# PicoHAL.net
KiCad netlist of a schematic drawn in Altium Designer
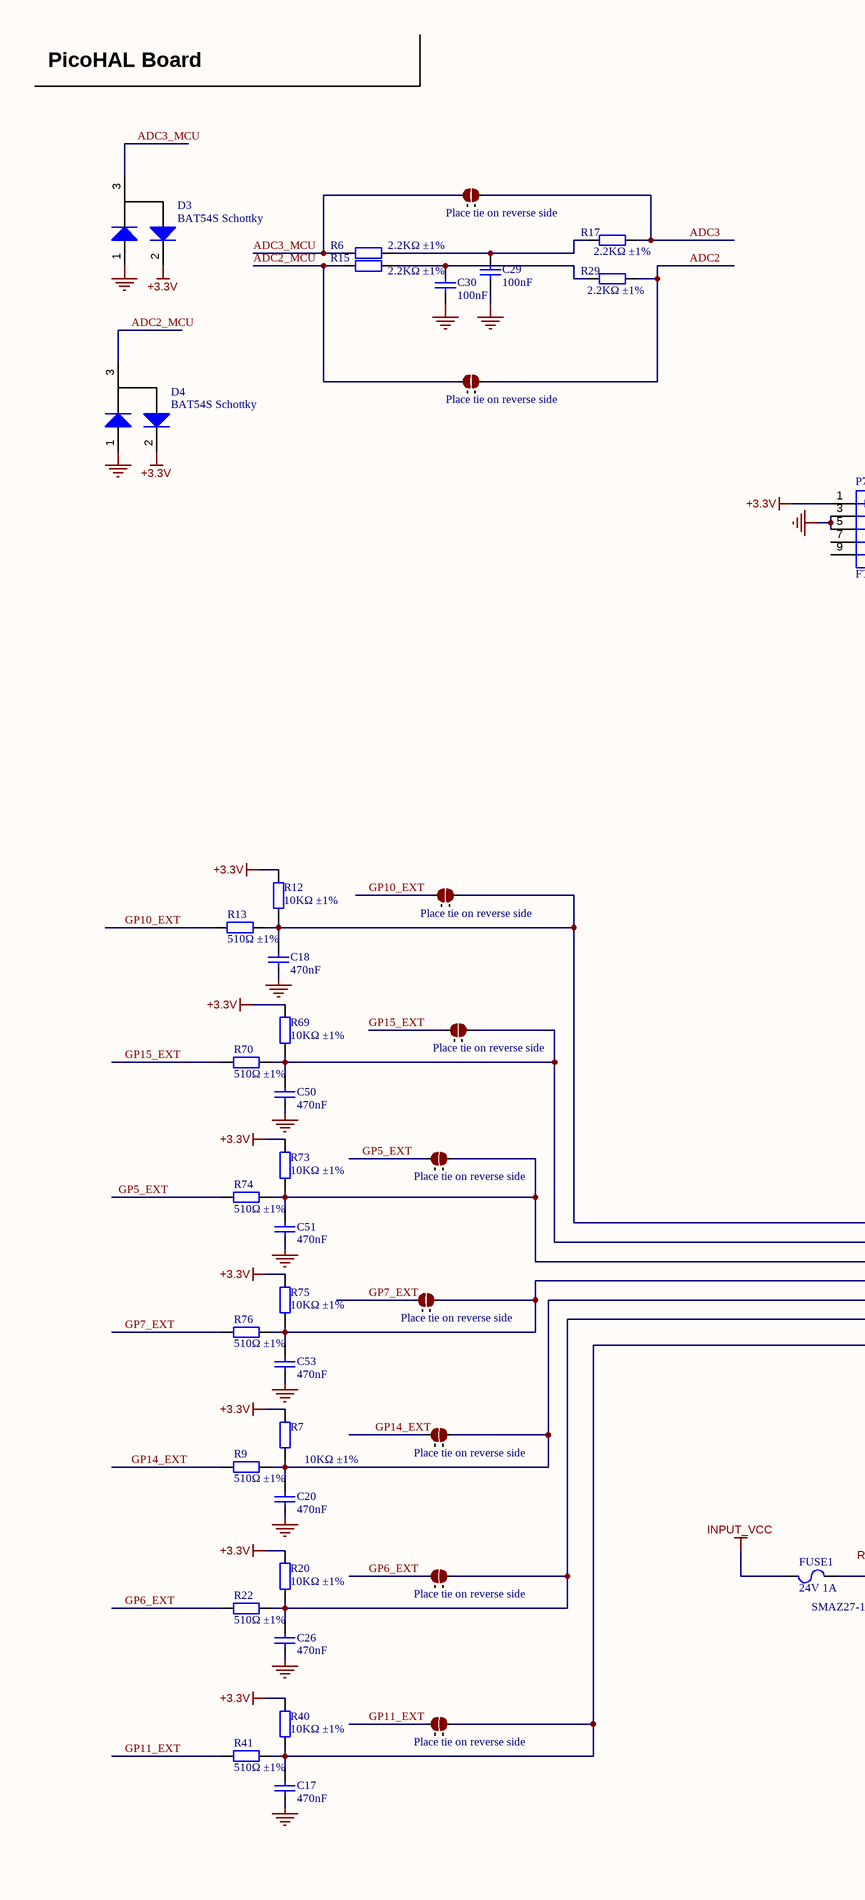
[diagram p0: PicoHAL.SchDoc, left]
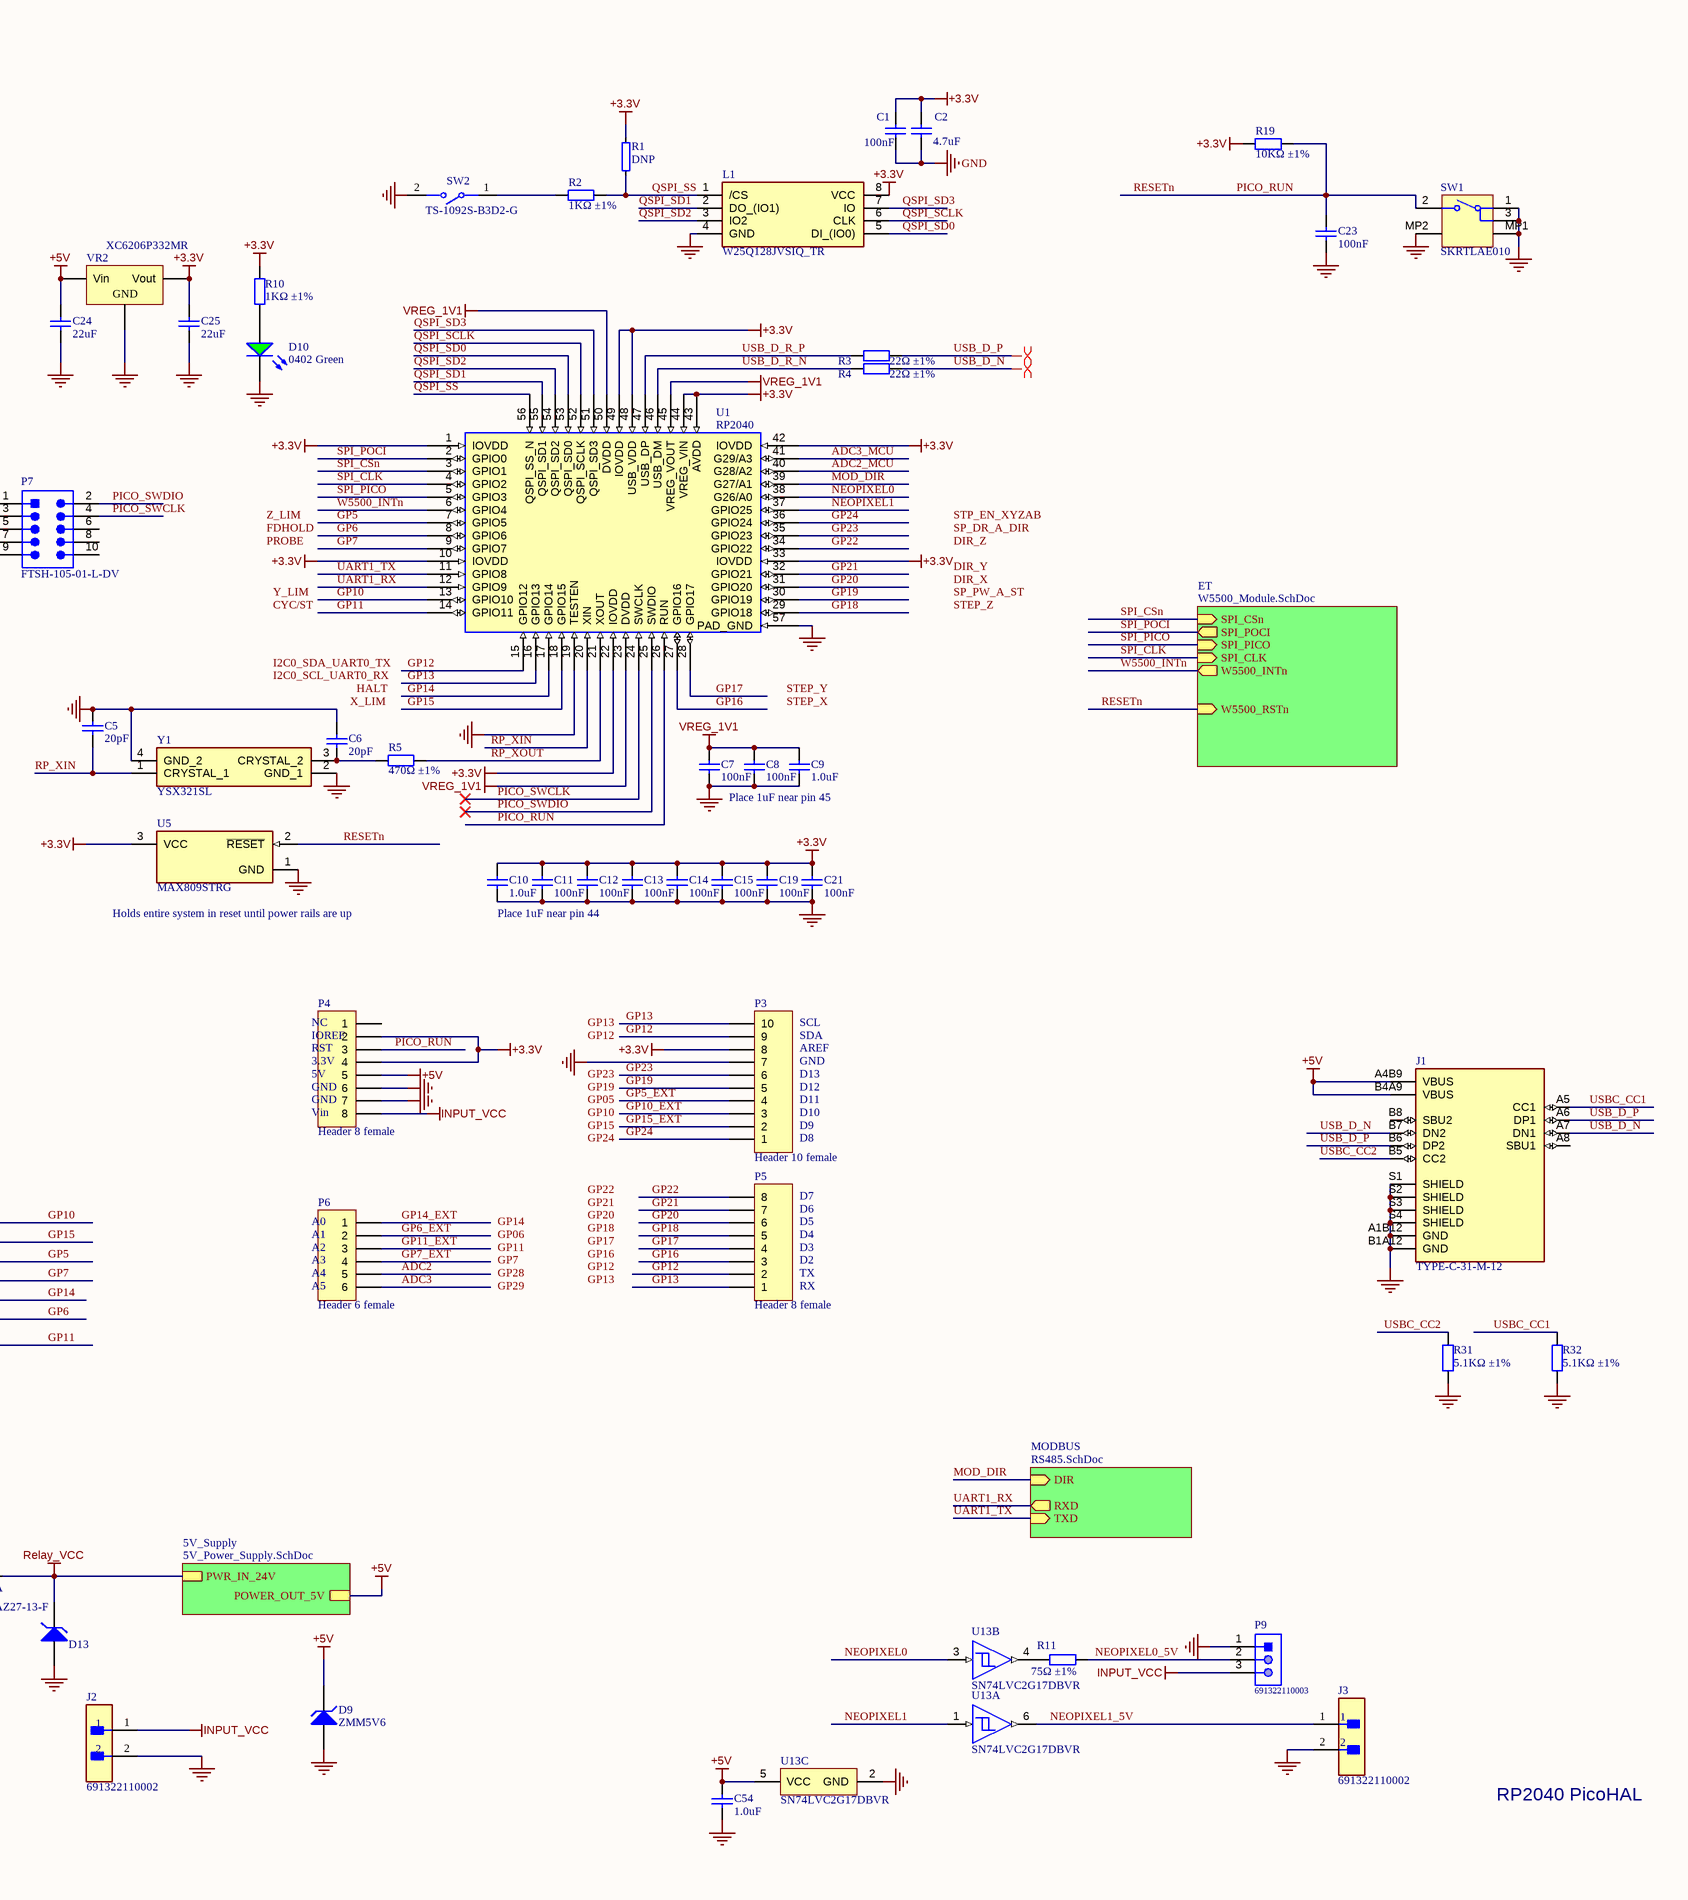
[diagram p1: PicoHAL.SchDoc, right]

(export (version "E")
  (design (tool "Eeschema 10.0.6"))
  (components
    (comp (ref "C1")
      (value "100nF")
      (footprint "0402_C")
      (description "Chip capacitors")
      (fields
        (field (name "MANUFACTURER") "Samsung Electro-Mechanics")
        (field (name "PARTNUMBER") "CL05B104KO5NNNC")
      )
      (libsource (lib "Cap") (part "0402 100nF (104) 10% 16V"))
    )
    (comp (ref "C2")
      (value "4.7uF")
      (footprint "0402_C")
      (description "Chip capacitor")
      (fields
        (field (name "MANUFACTURER") "Samsung Electro-Mechanics")
        (field (name "PARTNUMBER") "CL05A475MP5NRNC")
      )
      (libsource (lib "Cap") (part "0402 4.7uF (475) 20% 10V"))
    )
    (comp (ref "C5")
      (value "20pF")
      (footprint "0402_C")
      (description "Chip capacitors")
      (fields
        (field (name "MANUFACTURER") "Guangdong Fenghua Advanced Tech")
        (field (name "PARTNUMBER") "0402CG200J500NT")
      )
      (libsource (lib "Cap") (part "0402 20pF (200) 5% 50V"))
    )
    (comp (ref "C6")
      (value "20pF")
      (footprint "0402_C")
      (description "Chip capacitors")
      (fields
        (field (name "MANUFACTURER") "Guangdong Fenghua Advanced Tech")
        (field (name "PARTNUMBER") "0402CG200J500NT")
      )
      (libsource (lib "Cap") (part "0402 20pF (200) 5% 50V"))
    )
    (comp (ref "C7")
      (value "100nF")
      (footprint "0402_C")
      (description "Chip capacitors")
      (fields
        (field (name "MANUFACTURER") "Samsung Electro-Mechanics")
        (field (name "PARTNUMBER") "CL05B104KO5NNNC")
      )
      (libsource (lib "Cap") (part "0402 100nF (104) 10% 16V"))
    )
    (comp (ref "C8")
      (value "100nF")
      (footprint "0402_C")
      (description "Chip capacitors")
      (fields
        (field (name "MANUFACTURER") "Samsung Electro-Mechanics")
        (field (name "PARTNUMBER") "CL05B104KO5NNNC")
      )
      (libsource (lib "Cap") (part "0402 100nF (104) 10% 16V"))
    )
    (comp (ref "C9")
      (value "1.0uF")
      (footprint "0402_C")
      (description "Chip capacitor")
      (fields
        (field (name "MANUFACTURER") "Samsung Electro-Mechanics")
        (field (name "PARTNUMBER") "CL05A105KA5NQNC")
      )
      (libsource (lib "Cap") (part "0402 1.0uF (105) 10% 25V"))
    )
    (comp (ref "C10")
      (value "1.0uF")
      (footprint "0402_C")
      (description "Chip capacitor")
      (fields
        (field (name "MANUFACTURER") "Samsung Electro-Mechanics")
        (field (name "PARTNUMBER") "CL05A105KA5NQNC")
      )
      (libsource (lib "Cap") (part "0402 1.0uF (105) 10% 25V"))
    )
    (comp (ref "C11")
      (value "100nF")
      (footprint "0402_C")
      (description "Chip capacitors")
      (fields
        (field (name "MANUFACTURER") "Samsung Electro-Mechanics")
        (field (name "PARTNUMBER") "CL05B104KO5NNNC")
      )
      (libsource (lib "Cap") (part "0402 100nF (104) 10% 16V"))
    )
    (comp (ref "C12")
      (value "100nF")
      (footprint "0402_C")
      (description "Chip capacitors")
      (fields
        (field (name "MANUFACTURER") "Samsung Electro-Mechanics")
        (field (name "PARTNUMBER") "CL05B104KO5NNNC")
      )
      (libsource (lib "Cap") (part "0402 100nF (104) 10% 16V"))
    )
    (comp (ref "C13")
      (value "100nF")
      (footprint "0402_C")
      (description "Chip capacitors")
      (fields
        (field (name "MANUFACTURER") "Samsung Electro-Mechanics")
        (field (name "PARTNUMBER") "CL05B104KO5NNNC")
      )
      (libsource (lib "Cap") (part "0402 100nF (104) 10% 16V"))
    )
    (comp (ref "C14")
      (value "100nF")
      (footprint "0402_C")
      (description "Chip capacitors")
      (fields
        (field (name "MANUFACTURER") "Samsung Electro-Mechanics")
        (field (name "PARTNUMBER") "CL05B104KO5NNNC")
      )
      (libsource (lib "Cap") (part "0402 100nF (104) 10% 16V"))
    )
    (comp (ref "C15")
      (value "100nF")
      (footprint "0402_C")
      (description "Chip capacitors")
      (fields
        (field (name "MANUFACTURER") "Samsung Electro-Mechanics")
        (field (name "PARTNUMBER") "CL05B104KO5NNNC")
      )
      (libsource (lib "Cap") (part "0402 100nF (104) 10% 16V"))
    )
    (comp (ref "C17")
      (value "470nF")
      (footprint "0402_C")
      (description "Chip capacitors")
      (fields
        (field (name "MANUFACTURER") "Samsung Electro-Mechanics")
        (field (name "PARTNUMBER") "CL05A474KP5NNNC")
      )
      (libsource (lib "Cap") (part "0402 470nF (474) 10% 10V"))
    )
    (comp (ref "C18")
      (value "470nF")
      (footprint "0402_C")
      (description "Chip capacitors")
      (fields
        (field (name "MANUFACTURER") "Samsung Electro-Mechanics")
        (field (name "PARTNUMBER") "CL05A474KP5NNNC")
      )
      (libsource (lib "Cap") (part "0402 470nF (474) 10% 10V"))
    )
    (comp (ref "C19")
      (value "100nF")
      (footprint "0402_C")
      (description "Chip capacitors")
      (fields
        (field (name "MANUFACTURER") "Samsung Electro-Mechanics")
        (field (name "PARTNUMBER") "CL05B104KO5NNNC")
      )
      (libsource (lib "Cap") (part "0402 100nF (104) 10% 16V"))
    )
    (comp (ref "C20")
      (value "470nF")
      (footprint "0402_C")
      (description "Chip capacitors")
      (fields
        (field (name "MANUFACTURER") "Samsung Electro-Mechanics")
        (field (name "PARTNUMBER") "CL05A474KP5NNNC")
      )
      (libsource (lib "Cap") (part "0402 470nF (474) 10% 10V"))
    )
    (comp (ref "C21")
      (value "100nF")
      (footprint "0402_C")
      (description "Chip capacitors")
      (fields
        (field (name "MANUFACTURER") "Samsung Electro-Mechanics")
        (field (name "PARTNUMBER") "CL05B104KO5NNNC")
      )
      (libsource (lib "Cap") (part "0402 100nF (104) 10% 16V"))
    )
    (comp (ref "C23")
      (value "100nF")
      (footprint "0402_C")
      (description "Chip capacitors")
      (fields
        (field (name "MANUFACTURER") "Samsung Electro-Mechanics")
        (field (name "PARTNUMBER") "CL05B104KO5NNNC")
      )
      (libsource (lib "Cap") (part "0402 100nF (104) 10% 16V"))
    )
    (comp (ref "C24")
      (value "22uF")
      (footprint "0805_C")
      (description "Chip capacitors")
      (fields
        (field (name "MANUFACTURER") "Samsung Electro-Mechanics")
        (field (name "PARTNUMBER") "CL21A226MAQNNNE")
      )
      (libsource (lib "Cap") (part "0805 22uF (226) 20% 25V"))
    )
    (comp (ref "C25")
      (value "22uF")
      (footprint "0805_C")
      (description "Chip capacitors")
      (fields
        (field (name "MANUFACTURER") "Samsung Electro-Mechanics")
        (field (name "PARTNUMBER") "CL21A226MAQNNNE")
      )
      (libsource (lib "Cap") (part "0805 22uF (226) 20% 25V"))
    )
    (comp (ref "C26")
      (value "470nF")
      (footprint "0402_C")
      (description "Chip capacitors")
      (fields
        (field (name "MANUFACTURER") "Samsung Electro-Mechanics")
        (field (name "PARTNUMBER") "CL05A474KP5NNNC")
      )
      (libsource (lib "Cap") (part "0402 470nF (474) 10% 10V"))
    )
    (comp (ref "C29")
      (value "100nF")
      (footprint "0402_C")
      (description "Chip capacitors")
      (fields
        (field (name "MANUFACTURER") "Samsung Electro-Mechanics")
        (field (name "PARTNUMBER") "CL05B104KO5NNNC")
      )
      (libsource (lib "Cap") (part "0402 100nF (104) 10% 16V"))
    )
    (comp (ref "C30")
      (value "100nF")
      (footprint "0402_C")
      (description "Chip capacitors")
      (fields
        (field (name "MANUFACTURER") "Samsung Electro-Mechanics")
        (field (name "PARTNUMBER") "CL05B104KO5NNNC")
      )
      (libsource (lib "Cap") (part "0402 100nF (104) 10% 16V"))
    )
    (comp (ref "C50")
      (value "470nF")
      (footprint "0402_C")
      (description "Chip capacitors")
      (fields
        (field (name "MANUFACTURER") "Samsung Electro-Mechanics")
        (field (name "PARTNUMBER") "CL05A474KP5NNNC")
      )
      (libsource (lib "Cap") (part "0402 470nF (474) 10% 10V"))
    )
    (comp (ref "C51")
      (value "470nF")
      (footprint "0402_C")
      (description "Chip capacitors")
      (fields
        (field (name "MANUFACTURER") "Samsung Electro-Mechanics")
        (field (name "PARTNUMBER") "CL05A474KP5NNNC")
      )
      (libsource (lib "Cap") (part "0402 470nF (474) 10% 10V"))
    )
    (comp (ref "C53")
      (value "470nF")
      (footprint "0402_C")
      (description "Chip capacitors")
      (fields
        (field (name "MANUFACTURER") "Samsung Electro-Mechanics")
        (field (name "PARTNUMBER") "CL05A474KP5NNNC")
      )
      (libsource (lib "Cap") (part "0402 470nF (474) 10% 10V"))
    )
    (comp (ref "C54")
      (value "1.0uF")
      (footprint "0402_C")
      (description "Chip capacitor")
      (fields
        (field (name "MANUFACTURER") "Samsung Electro-Mechanics")
        (field (name "PARTNUMBER") "CL05A105KA5NQNC")
      )
      (libsource (lib "Cap") (part "0402 1.0uF (105) 10% 25V"))
    )
    (comp (ref "D3")
      (value "BAT54S Schottky")
      (footprint "SOT-23(SOT-23-3)")
      (description "30V Dual 200mA 800mV@100mA SOT-23 Schottky Barrier Diodes (SBD) ROHS")
      (libsource (lib "Diode") (part "SOT-23 BAT54S"))
    )
    (comp (ref "D4")
      (value "BAT54S Schottky")
      (footprint "SOT-23(SOT-23-3)")
      (description "30V Dual 200mA 800mV@100mA SOT-23 Schottky Barrier Diodes (SBD) ROHS")
      (libsource (lib "Diode") (part "SOT-23 BAT54S"))
    )
    (comp (ref "D9")
      (value "ZMM5V6")
      (footprint "LL-34")
      (description "500mW - 0.1uA @ 1V 5.6V LL-34 Zener Diodes ROHS")
      (libsource (lib "Zener") (part "LL-34 ZMM5V6"))
    )
    (comp (ref "D10")
      (value "0402 Green")
      (footprint "LED 0402_1005 RED")
      (description "LED")
      (libsource (lib "LED") (part "0402 LED Green"))
    )
    (comp (ref "D13")
      (value "SMAZ27-13-F")
      (footprint "DIOM5226X240N")
      (description "27V ±5% 1W 500nA @ 20.5V SMA(DO-214AC) Zener Diodes RoHS")
      (libsource (lib "PrintNC_GRBLHAL_Breakout") (part "BZT52C27"))
    )
    (comp (ref "FUSE1")
      (value "24V 1A")
      (footprint "1206_C")
      (description "24V 1A 0.1s 1206 PTC Resettable Fuses RoHS")
      (fields
        (field (name "MANUFACTURER") "Jinrui Electronic Materials Co.")
        (field (name "PARTNUMBER") "JK-nSMD050-24")
      )
      (libsource (lib "PrintNC_GRBLHAL_Breakout") (part "JK-nSMD050-24"))
    )
    (comp (ref "J1")
      (value "TYPE-C-31-M-12")
      (footprint "HRO_TYPE-C-31-M-12")
      (description "USB Connectors 24 Receptacle 1 8.94*7.3mm RoHS")
      (fields (field (name "MF") "HRO Electronics Co., Ltd."))
      (libsource (lib "Universal_CNC_Breakout") (part "TYPE-C-31-M-12"))
    )
    (comp (ref "J2")
      (value "691322110002")
      (footprint "FP-691322110002-MFG")
      (description "TERM BLOCK HDR 2POS 90DEG 3.5MM")
      (fields (field (name "VOLTAGE") "300V"))
      (libsource (lib "") (part "3bc925449376181038e59eaffc5286c_1"))
    )
    (comp (ref "J3")
      (value "691322110002")
      (footprint "FP-691322110002-MFG")
      (description "TERM BLOCK HDR 2POS 90DEG 3.5MM")
      (libsource (lib "Altium Content Vault") (part "3bc925449376181038e59eaffc5286c"))
    )
    (comp (ref "J7")
      (value "2 way net solder junction - Normally Open")
      (footprint "2waySolder_NO")
      (libsource (lib "PrintNC_GRBLHAL_Breakout") (part "2waySolderNO"))
    )
    (comp (ref "J8")
      (value "2 way net solder junction - Normally Open")
      (footprint "2waySolder_NO")
      (libsource (lib "PrintNC_GRBLHAL_Breakout") (part "2waySolderNO"))
    )
    (comp (ref "J9")
      (value "2 way net solder junction - Normally Open")
      (footprint "2waySolder_NO")
      (libsource (lib "PrintNC_GRBLHAL_Breakout") (part "2waySolderNO"))
    )
    (comp (ref "J10")
      (value "2 way net solder junction - Normally Open")
      (footprint "2waySolder_NO")
      (libsource (lib "PrintNC_GRBLHAL_Breakout") (part "2waySolderNO"))
    )
    (comp (ref "J11")
      (value "2 way net solder junction - Normally Open")
      (footprint "2waySolder_NO")
      (libsource (lib "PrintNC_GRBLHAL_Breakout") (part "2waySolderNO"))
    )
    (comp (ref "J12")
      (value "2 way net solder junction - Normally Open")
      (footprint "2waySolder_NO")
      (libsource (lib "PrintNC_GRBLHAL_Breakout") (part "2waySolderNO"))
    )
    (comp (ref "J13")
      (value "2 way net solder junction - Normally Open")
      (footprint "2waySolder_NO")
      (libsource (lib "PrintNC_GRBLHAL_Breakout") (part "2waySolderNO"))
    )
    (comp (ref "J14")
      (value "2 way net solder junction - Normally Open")
      (footprint "2waySolder_NO")
      (libsource (lib "PrintNC_GRBLHAL_Breakout") (part "2waySolderNO"))
    )
    (comp (ref "J15")
      (value "2 way net solder junction - Normally Open")
      (footprint "2waySolder_NO")
      (libsource (lib "PrintNC_GRBLHAL_Breakout") (part "2waySolderNO"))
    )
    (comp (ref "L1")
      (value "W25Q128JVSIQ_TR")
      (footprint "SamacSys:SOIC127P780X195-8N")
      (description "Inductor")
      (fields
        (field (name "MANUFACTURER_PART_NUMBER") "W25Q128JVSIQ TR")
        (field (name "MOUSER PART NUMBER") "454-W25Q128JVSIQTR")
      )
      (libsource (lib "*") (part "W25Q128JVSIQ_TR"))
    )
    (comp (ref "P3")
      (value "Header 10 female")
      (footprint "HDR1X10")
      (description "Header, 10-Pin")
      (fields (field (name "PUBLISHER") "Altium Limited"))
      (libsource (lib "Miscellaneous Connectors") (part "Header 10"))
    )
    (comp (ref "P4")
      (value "Header 8 female")
      (footprint "HDR1X8")
      (description "Header, 8-Pin")
      (fields (field (name "PUBLISHER") "Altium Limited"))
      (libsource (lib "") (part "Header 8_1"))
    )
    (comp (ref "P5")
      (value "Header 8 female")
      (footprint "HDR1X8")
      (description "Header, 8-Pin")
      (fields (field (name "PUBLISHER") "Altium Limited"))
      (libsource (lib "Miscellaneous Connectors") (part "Header 8"))
    )
    (comp (ref "P6")
      (value "Header 6 female")
      (footprint "HDR1X6")
      (description "Header, 6-Pin")
      (fields (field (name "PUBLISHER") "Altium Limited"))
      (libsource (lib "Miscellaneous Connectors") (part "Header 6"))
    )
    (comp (ref "P7")
      (value "FTSH-105-01-L-DV")
      (footprint "SMTC-FTSH-105-01-L-DV_V")
      (description "Male Header, Pitch 1.27 mm, 2 x 5 Position, Height 5.96 mm, -55 to 125 degC, RoHS, Bulk")
      (fields (field (name "MANUFACTURER") "Samtec"))
      (libsource (lib "Altium Content Vault") (part "CN-2P-M-R10"))
    )
    (comp (ref "P9")
      (value "691322110003")
      (footprint "691322110003")
      (description "Serie 3221 - 3.50mm Horizontal PCB Header WR-TBL, 3 pin")
      (libsource (lib "Altium Content Vault") (part "WE-CN-1P-M-R3"))
    )
    (comp (ref "R1")
      (value "DNP")
      (footprint "0402")
      (description "Resistor, ±5%, 0.05W")
      (fields (field (name "PART NUMBER") "R0201-0R") (field (name "PUBLISHER") "Nordic Semiconductor"))
      (libsource (lib "Passives") (part "RES"))
    )
    (comp (ref "R2")
      (value "1KΩ ±1%")
      (footprint "0402_R")
      (description "Chip resistor")
      (fields (field (name "MANUFACTURER") "Uniroyal Elec") (field (name "PARTNUMBER") "0402WGF1001TCE"))
      (libsource (lib "RES") (part "0402 1K (1001) 1%"))
    )
    (comp (ref "R3")
      (value "22Ω ±1%")
      (footprint "0402_R")
      (description "Chip resistor")
      (fields (field (name "MANUFACTURER") "Uniroyal Elec") (field (name "PARTNUMBER") "0402WGF220JTCE"))
      (libsource (lib "RES") (part "0402 22R (22R0) 1%"))
    )
    (comp (ref "R4")
      (value "22Ω ±1%")
      (footprint "0402_R")
      (description "Chip resistor")
      (fields (field (name "MANUFACTURER") "Uniroyal Elec") (field (name "PARTNUMBER") "0402WGF220JTCE"))
      (libsource (lib "RES") (part "0402 22R (22R0) 1%"))
    )
    (comp (ref "R5")
      (value "470Ω ±1%")
      (footprint "0402_R")
      (description "Chip resistor")
      (fields (field (name "MANUFACTURER") "Uniroyal Elec") (field (name "PARTNUMBER") "0402WGF4700TCE"))
      (libsource (lib "RES") (part "0402 470R (4700) 1%"))
    )
    (comp (ref "R6")
      (value "2.2KΩ ±1%")
      (footprint "0402_R")
      (description "Chip resistor")
      (fields (field (name "MANUFACTURER") "Uniroyal Elec") (field (name "PARTNUMBER") "0402WGF2201TCE"))
      (libsource (lib "RES") (part "0402 2.2K (2201) 1%"))
    )
    (comp (ref "R7")
      (value "10KΩ ±1%")
      (footprint "0402_R")
      (description "Chip resistor")
      (fields (field (name "MANUFACTURER") "Uniroyal Elec") (field (name "PARTNUMBER") "0402WGF1002TCE"))
      (libsource (lib "RES") (part "0402 10K (1002) 1%"))
    )
    (comp (ref "R9")
      (value "510Ω ±1%")
      (footprint "0402_R")
      (description "Chip resistor")
      (fields (field (name "MANUFACTURER") "Uniroyal Elec") (field (name "PARTNUMBER") "0402WGF5100TCE"))
      (libsource (lib "RES") (part "0402 510R (5100) 1%"))
    )
    (comp (ref "R10")
      (value "1KΩ ±1%")
      (footprint "0402_R")
      (description "Chip resistor")
      (fields (field (name "MANUFACTURER") "Uniroyal Elec") (field (name "PARTNUMBER") "0402WGF1001TCE"))
      (libsource (lib "") (part "0402 1K (1001) 1%_1"))
    )
    (comp (ref "R11")
      (value "75Ω ±1%")
      (footprint "0402_R")
      (description "Chip resistor")
      (fields (field (name "MANUFACTURER") "Uniroyal Elec") (field (name "PARTNUMBER") "0402WGF750JTCE"))
      (libsource (lib "RES") (part "0402 75R (75R0) 1%"))
    )
    (comp (ref "R12")
      (value "10KΩ ±1%")
      (footprint "0402_R")
      (description "Chip resistor")
      (fields (field (name "MANUFACTURER") "Uniroyal Elec") (field (name "PARTNUMBER") "0402WGF1002TCE"))
      (libsource (lib "RES") (part "0402 10K (1002) 1%"))
    )
    (comp (ref "R13")
      (value "510Ω ±1%")
      (footprint "0402_R")
      (description "Chip resistor")
      (fields (field (name "MANUFACTURER") "Uniroyal Elec") (field (name "PARTNUMBER") "0402WGF5100TCE"))
      (libsource (lib "RES") (part "0402 510R (5100) 1%"))
    )
    (comp (ref "R15")
      (value "2.2KΩ ±1%")
      (footprint "0402_R")
      (description "Chip resistor")
      (fields (field (name "MANUFACTURER") "Uniroyal Elec") (field (name "PARTNUMBER") "0402WGF2201TCE"))
      (libsource (lib "RES") (part "0402 2.2K (2201) 1%"))
    )
    (comp (ref "R17")
      (value "2.2KΩ ±1%")
      (footprint "0402_R")
      (description "Chip resistor")
      (fields (field (name "MANUFACTURER") "Uniroyal Elec") (field (name "PARTNUMBER") "0402WGF2201TCE"))
      (libsource (lib "RES") (part "0402 2.2K (2201) 1%"))
    )
    (comp (ref "R19")
      (value "10KΩ ±1%")
      (footprint "0402_R")
      (description "Chip resistor")
      (fields (field (name "MANUFACTURER") "Uniroyal Elec") (field (name "PARTNUMBER") "0402WGF1002TCE"))
      (libsource (lib "") (part "0402 10K (1002) 1%_1"))
    )
    (comp (ref "R20")
      (value "10KΩ ±1%")
      (footprint "0402_R")
      (description "Chip resistor")
      (fields (field (name "MANUFACTURER") "Uniroyal Elec") (field (name "PARTNUMBER") "0402WGF1002TCE"))
      (libsource (lib "RES") (part "0402 10K (1002) 1%"))
    )
    (comp (ref "R22")
      (value "510Ω ±1%")
      (footprint "0402_R")
      (description "Chip resistor")
      (fields (field (name "MANUFACTURER") "Uniroyal Elec") (field (name "PARTNUMBER") "0402WGF5100TCE"))
      (libsource (lib "RES") (part "0402 510R (5100) 1%"))
    )
    (comp (ref "R29")
      (value "2.2KΩ ±1%")
      (footprint "0402_R")
      (description "Chip resistor")
      (fields (field (name "MANUFACTURER") "Uniroyal Elec") (field (name "PARTNUMBER") "0402WGF2201TCE"))
      (libsource (lib "RES") (part "0402 2.2K (2201) 1%"))
    )
    (comp (ref "R31")
      (value "5.1KΩ ±1%")
      (footprint "0402_R")
      (description "Chip resistor")
      (fields (field (name "MANUFACTURER") "Uniroyal Elec") (field (name "PARTNUMBER") "0402WGF5101TCE"))
      (libsource (lib "RES") (part "0402 5.1K (5101) 1%"))
    )
    (comp (ref "R32")
      (value "5.1KΩ ±1%")
      (footprint "0402_R")
      (description "Chip resistor")
      (fields (field (name "MANUFACTURER") "Uniroyal Elec") (field (name "PARTNUMBER") "0402WGF5101TCE"))
      (libsource (lib "RES") (part "0402 5.1K (5101) 1%"))
    )
    (comp (ref "R40")
      (value "10KΩ ±1%")
      (footprint "0402_R")
      (description "Chip resistor")
      (fields (field (name "MANUFACTURER") "Uniroyal Elec") (field (name "PARTNUMBER") "0402WGF1002TCE"))
      (libsource (lib "RES") (part "0402 10K (1002) 1%"))
    )
    (comp (ref "R41")
      (value "510Ω ±1%")
      (footprint "0402_R")
      (description "Chip resistor")
      (fields (field (name "MANUFACTURER") "Uniroyal Elec") (field (name "PARTNUMBER") "0402WGF5100TCE"))
      (libsource (lib "RES") (part "0402 510R (5100) 1%"))
    )
    (comp (ref "R69")
      (value "10KΩ ±1%")
      (footprint "0402_R")
      (description "Chip resistor")
      (fields (field (name "MANUFACTURER") "Uniroyal Elec") (field (name "PARTNUMBER") "0402WGF1002TCE"))
      (libsource (lib "RES") (part "0402 10K (1002) 1%"))
    )
    (comp (ref "R70")
      (value "510Ω ±1%")
      (footprint "0402_R")
      (description "Chip resistor")
      (fields (field (name "MANUFACTURER") "Uniroyal Elec") (field (name "PARTNUMBER") "0402WGF5100TCE"))
      (libsource (lib "RES") (part "0402 510R (5100) 1%"))
    )
    (comp (ref "R73")
      (value "10KΩ ±1%")
      (footprint "0402_R")
      (description "Chip resistor")
      (fields (field (name "MANUFACTURER") "Uniroyal Elec") (field (name "PARTNUMBER") "0402WGF1002TCE"))
      (libsource (lib "RES") (part "0402 10K (1002) 1%"))
    )
    (comp (ref "R74")
      (value "510Ω ±1%")
      (footprint "0402_R")
      (description "Chip resistor")
      (fields (field (name "MANUFACTURER") "Uniroyal Elec") (field (name "PARTNUMBER") "0402WGF5100TCE"))
      (libsource (lib "RES") (part "0402 510R (5100) 1%"))
    )
    (comp (ref "R75")
      (value "10KΩ ±1%")
      (footprint "0402_R")
      (description "Chip resistor")
      (fields (field (name "MANUFACTURER") "Uniroyal Elec") (field (name "PARTNUMBER") "0402WGF1002TCE"))
      (libsource (lib "RES") (part "0402 10K (1002) 1%"))
    )
    (comp (ref "R76")
      (value "510Ω ±1%")
      (footprint "0402_R")
      (description "Chip resistor")
      (fields (field (name "MANUFACTURER") "Uniroyal Elec") (field (name "PARTNUMBER") "0402WGF5100TCE"))
      (libsource (lib "RES") (part "0402 510R (5100) 1%"))
    )
    (comp (ref "SW1")
      (value "SKRTLAE010")
      (footprint "ALPS-SKRTLAE010_V")
      (description "Side Push Type, 250 V, -40 to 90 degC, 3-Pin SMD, RoHS, Tape and Reel")
      (fields (field (name "MANUFACTURER") "ALPS"))
      (libsource (lib "Altium Content Vault") (part "SW_SPST-3_A"))
    )
    (comp (ref "SW2")
      (value "TS-1092S-B3D2-G")
      (footprint "SW-SMD_L6.1-W3.6-LS7.9")
      (description "Tactile Switches  3.6mm 2.5mm Rectangle button Brick nogging SPST 6.1mm 250gf SMD ROHS")
      (libsource (lib "Universal_CNC_Breakout") (part "TS-1092S-B3D2-G"))
    )
    (comp (ref "U1")
      (value "RP2040")
      (footprint "RP2040")
      (description "RP2040 First MCU from RPI")
      (libsource (lib "Universal_CNC_Breakout") (part "RP2040"))
    )
    (comp (ref "U5")
      (value "MAX809STRG")
      (footprint "FP-318-08-MFG")
      (description "IC MPU SUPERVISORY 2.93V SOT23")
      (fields
        (field (name "OCTOPART") "https://octopart.com/max809strg-on+semiconductor-509853")
        (field (name "MANUFACTURER") "ON SEMICONDUCTOR")
      )
      (libsource (lib "Altium Content Vault") (part "10e2fe7115e7b167e7ed62dcbcd754e"))
    )
    (comp (ref "U13")
      (value "SN74LVC2G17DBVR")
      (footprint "DBV0006A_N")
      (description "Dual Schmitt-Trigger Buffer, DBV0006A, LARGE T&R")
      (fields
        (field (name "GENERIC PART NUMBER") "SN74LVC2G17")
        (field (name "MANUFACTURER") "Texas Instruments")
      )
      (libsource (lib "Altium Content Vault") (part "TI-SN74XXX2GXXX-6_A-SCHMITT"))
    )
    (comp (ref "VR2")
      (value "XC6206P332MR")
      (footprint "SOT-23-3L")
      (description "200mA 680mV@(100mA) Fixed 3.3V~3.3V Positive 1 6V SOT-23-3L Linear Voltage Regulators (LDO) ROHS")
      (libsource (lib "LDO") (part "SOT-23 XC6206P332MR"))
    )
    (comp (ref "Y1")
      (value "YSX321SL")
      (footprint "SamacSys:YSX321SL")
      (description "Crystal or Oscillator")
      (libsource (lib "*") (part "YSX321SL"))
    )
  )
  (nets
    (net (code "1") (name "+3.3V") (class "Default")
      (node (ref "C1") (pin "2") (pinfunction "2_2") (pintype "passive"))
      (node (ref "C10") (pin "2") (pinfunction "2_2") (pintype "passive"))
      (node (ref "C11") (pin "2") (pinfunction "2_2") (pintype "passive"))
      (node (ref "C12") (pin "2") (pinfunction "2_2") (pintype "passive"))
      (node (ref "C13") (pin "2") (pinfunction "2_2") (pintype "passive"))
      (node (ref "C14") (pin "2") (pinfunction "2_2") (pintype "passive"))
      (node (ref "C15") (pin "2") (pinfunction "2_2") (pintype "passive"))
      (node (ref "C19") (pin "2") (pinfunction "2_2") (pintype "passive"))
      (node (ref "C2") (pin "2") (pinfunction "2_2") (pintype "passive"))
      (node (ref "C21") (pin "2") (pinfunction "2_2") (pintype "passive"))
      (node (ref "C25") (pin "2") (pinfunction "2_2") (pintype "passive"))
      (node (ref "D3") (pin "2") (pinfunction "A_2") (pintype "passive"))
      (node (ref "D4") (pin "2") (pinfunction "A_2") (pintype "passive"))
      (node (ref "L1") (pin "8") (pinfunction "VCC_8") (pintype "passive"))
      (node (ref "P3") (pin "8") (pinfunction "8_8") (pintype "passive"))
      (node (ref "P4") (pin "2") (pinfunction "2_2") (pintype "passive"))
      (node (ref "P4") (pin "4") (pinfunction "4_4") (pintype "passive"))
      (node (ref "P7") (pin "1") (pinfunction "1_1") (pintype "passive"))
      (node (ref "R1") (pin "2") (pinfunction "2_2") (pintype "passive"))
      (node (ref "R10") (pin "2") (pinfunction "2_2") (pintype "passive"))
      (node (ref "R12") (pin "2") (pinfunction "2_2") (pintype "passive"))
      (node (ref "R19") (pin "2") (pinfunction "2_2") (pintype "passive"))
      (node (ref "R20") (pin "2") (pinfunction "2_2") (pintype "passive"))
      (node (ref "R40") (pin "2") (pinfunction "2_2") (pintype "passive"))
      (node (ref "R69") (pin "2") (pinfunction "2_2") (pintype "passive"))
      (node (ref "R7") (pin "2") (pinfunction "2_2") (pintype "passive"))
      (node (ref "R73") (pin "2") (pinfunction "2_2") (pintype "passive"))
      (node (ref "R75") (pin "2") (pinfunction "2_2") (pintype "passive"))
      (node (ref "U1") (pin "1") (pinfunction "IOVDD_1") (pintype "input"))
      (node (ref "U1") (pin "10") (pinfunction "IOVDD_10") (pintype "input"))
      (node (ref "U1") (pin "22") (pinfunction "IOVDD_22") (pintype "input"))
      (node (ref "U1") (pin "33") (pinfunction "IOVDD_33") (pintype "input"))
      (node (ref "U1") (pin "42") (pinfunction "IOVDD_42") (pintype "input"))
      (node (ref "U1") (pin "43") (pinfunction "AVDD_43") (pintype "input"))
      (node (ref "U1") (pin "44") (pinfunction "VREG_VIN_44") (pintype "input"))
      (node (ref "U1") (pin "48") (pinfunction "USB_VDD_48") (pintype "input"))
      (node (ref "U1") (pin "49") (pinfunction "IOVDD_49") (pintype "input"))
      (node (ref "U5") (pin "3") (pinfunction "VCC_3") (pintype "power_in"))
      (node (ref "VR2") (pin "2") (pinfunction "Vout_2") (pintype "passive"))
    )
    (net (code "2") (name "+5V") (class "Default")
      (node (ref "C24") (pin "2") (pinfunction "2_2") (pintype "passive"))
      (node (ref "C54") (pin "1") (pinfunction "1_1") (pintype "passive"))
      (node (ref "D9") (pin "2") (pinfunction "K_2") (pintype "passive"))
      (node (ref "J1") (pin "A4B9") (pinfunction "VBUS_A4B9") (pintype "power_in"))
      (node (ref "J1") (pin "B4A9") (pinfunction "VBUS_B4A9") (pintype "power_in"))
      (node (ref "P4") (pin "5") (pinfunction "5_5") (pintype "passive"))
      (node (ref "U13") (pin "5") (pinfunction "VCC_5") (pintype "power_in"))
      (node (ref "VR2") (pin "3") (pinfunction "Vin_3") (pintype "passive"))
    )
    (net (code "3") (name "/ADC2") (class "Default")
      (node (ref "J8") (pin "2") (pinfunction "2_2") (pintype "passive"))
      (node (ref "P6") (pin "5") (pinfunction "5_5") (pintype "passive"))
      (node (ref "R29") (pin "2") (pinfunction "2_2") (pintype "passive"))
    )
    (net (code "4") (name "/ADC2_MCU") (class "Default")
      (node (ref "D4") (pin "3") (pinfunction "K_3") (pintype "passive"))
      (node (ref "J8") (pin "1") (pinfunction "1_1") (pintype "passive"))
      (node (ref "R15") (pin "1") (pinfunction "1_1") (pintype "passive"))
      (node (ref "U1") (pin "40") (pinfunction "G28/A2_40") (pintype "bidirectional"))
    )
    (net (code "5") (name "/ADC3") (class "Default")
      (node (ref "J7") (pin "2") (pinfunction "2_2") (pintype "passive"))
      (node (ref "P6") (pin "6") (pinfunction "6_6") (pintype "passive"))
      (node (ref "R17") (pin "2") (pinfunction "2_2") (pintype "passive"))
    )
    (net (code "6") (name "/ADC3_MCU") (class "Default")
      (node (ref "D3") (pin "3") (pinfunction "K_3") (pintype "passive"))
      (node (ref "J7") (pin "1") (pinfunction "1_1") (pintype "passive"))
      (node (ref "R6") (pin "1") (pinfunction "1_1") (pintype "passive"))
      (node (ref "U1") (pin "41") (pinfunction "G29/A3_41") (pintype "bidirectional"))
    )
    (net (code "12") (name "/GP5") (class "Default")
      (node (ref "C51") (pin "2") (pinfunction "2_2") (pintype "passive"))
      (node (ref "J11") (pin "2") (pinfunction "2_2") (pintype "passive"))
      (node (ref "R73") (pin "1") (pinfunction "1_1") (pintype "passive"))
      (node (ref "R74") (pin "2") (pinfunction "2_2") (pintype "passive"))
      (node (ref "U1") (pin "7") (pinfunction "GPIO5_7") (pintype "bidirectional"))
    )
    (net (code "13") (name "/GP5_EXT") (class "Default")
      (node (ref "J11") (pin "1") (pinfunction "1_1") (pintype "passive"))
      (node (ref "P3") (pin "4") (pinfunction "4_4") (pintype "passive"))
      (node (ref "R74") (pin "1") (pinfunction "1_1") (pintype "passive"))
    )
    (net (code "14") (name "/GP6") (class "Default")
      (node (ref "C26") (pin "2") (pinfunction "2_2") (pintype "passive"))
      (node (ref "J14") (pin "2") (pinfunction "2_2") (pintype "passive"))
      (node (ref "R20") (pin "1") (pinfunction "1_1") (pintype "passive"))
      (node (ref "R22") (pin "2") (pinfunction "2_2") (pintype "passive"))
      (node (ref "U1") (pin "8") (pinfunction "GPIO6_8") (pintype "bidirectional"))
    )
    (net (code "15") (name "/GP6_EXT") (class "Default")
      (node (ref "J14") (pin "1") (pinfunction "1_1") (pintype "passive"))
      (node (ref "P6") (pin "2") (pinfunction "2_2") (pintype "passive"))
      (node (ref "R22") (pin "1") (pinfunction "1_1") (pintype "passive"))
    )
    (net (code "16") (name "/GP7") (class "Default")
      (node (ref "C53") (pin "2") (pinfunction "2_2") (pintype "passive"))
      (node (ref "J12") (pin "2") (pinfunction "2_2") (pintype "passive"))
      (node (ref "R75") (pin "1") (pinfunction "1_1") (pintype "passive"))
      (node (ref "R76") (pin "2") (pinfunction "2_2") (pintype "passive"))
      (node (ref "U1") (pin "9") (pinfunction "GPIO7_9") (pintype "bidirectional"))
    )
    (net (code "17") (name "/GP7_EXT") (class "Default")
      (node (ref "J12") (pin "1") (pinfunction "1_1") (pintype "passive"))
      (node (ref "P6") (pin "4") (pinfunction "4_4") (pintype "passive"))
      (node (ref "R76") (pin "1") (pinfunction "1_1") (pintype "passive"))
    )
    (net (code "18") (name "/GP10") (class "Default")
      (node (ref "C18") (pin "2") (pinfunction "2_2") (pintype "passive"))
      (node (ref "J9") (pin "2") (pinfunction "2_2") (pintype "passive"))
      (node (ref "R12") (pin "1") (pinfunction "1_1") (pintype "passive"))
      (node (ref "R13") (pin "2") (pinfunction "2_2") (pintype "passive"))
      (node (ref "U1") (pin "13") (pinfunction "GPIO10_13") (pintype "bidirectional"))
    )
    (net (code "19") (name "/GP10_EXT") (class "Default")
      (node (ref "J9") (pin "1") (pinfunction "1_1") (pintype "passive"))
      (node (ref "P3") (pin "3") (pinfunction "3_3") (pintype "passive"))
      (node (ref "R13") (pin "1") (pinfunction "1_1") (pintype "passive"))
    )
    (net (code "20") (name "/GP11") (class "Default")
      (node (ref "C17") (pin "2") (pinfunction "2_2") (pintype "passive"))
      (node (ref "J15") (pin "2") (pinfunction "2_2") (pintype "passive"))
      (node (ref "R40") (pin "1") (pinfunction "1_1") (pintype "passive"))
      (node (ref "R41") (pin "2") (pinfunction "2_2") (pintype "passive"))
      (node (ref "U1") (pin "14") (pinfunction "GPIO11_14") (pintype "bidirectional"))
    )
    (net (code "21") (name "/GP11_EXT") (class "Default")
      (node (ref "J15") (pin "1") (pinfunction "1_1") (pintype "passive"))
      (node (ref "P6") (pin "3") (pinfunction "3_3") (pintype "passive"))
      (node (ref "R41") (pin "1") (pinfunction "1_1") (pintype "passive"))
    )
    (net (code "22") (name "/GP12") (class "Default")
      (node (ref "P3") (pin "9") (pinfunction "9_9") (pintype "passive"))
      (node (ref "P5") (pin "2") (pinfunction "2_2") (pintype "passive"))
      (node (ref "U1") (pin "15") (pinfunction "GPIO12_15") (pintype "input"))
    )
    (net (code "23") (name "/GP13") (class "Default")
      (node (ref "P3") (pin "10") (pinfunction "10_10") (pintype "passive"))
      (node (ref "P5") (pin "1") (pinfunction "1_1") (pintype "passive"))
      (node (ref "U1") (pin "16") (pinfunction "GPIO13_16") (pintype "input"))
    )
    (net (code "24") (name "/GP14") (class "Default")
      (node (ref "C20") (pin "2") (pinfunction "2_2") (pintype "passive"))
      (node (ref "J13") (pin "2") (pinfunction "2_2") (pintype "passive"))
      (node (ref "R7") (pin "1") (pinfunction "1_1") (pintype "passive"))
      (node (ref "R9") (pin "2") (pinfunction "2_2") (pintype "passive"))
      (node (ref "U1") (pin "17") (pinfunction "GPIO14_17") (pintype "input"))
    )
    (net (code "25") (name "/GP14_EXT") (class "Default")
      (node (ref "J13") (pin "1") (pinfunction "1_1") (pintype "passive"))
      (node (ref "P6") (pin "1") (pinfunction "1_1") (pintype "passive"))
      (node (ref "R9") (pin "1") (pinfunction "1_1") (pintype "passive"))
    )
    (net (code "26") (name "/GP15") (class "Default")
      (node (ref "C50") (pin "2") (pinfunction "2_2") (pintype "passive"))
      (node (ref "J10") (pin "2") (pinfunction "2_2") (pintype "passive"))
      (node (ref "R69") (pin "1") (pinfunction "1_1") (pintype "passive"))
      (node (ref "R70") (pin "2") (pinfunction "2_2") (pintype "passive"))
      (node (ref "U1") (pin "18") (pinfunction "GPIO15_18") (pintype "input"))
    )
    (net (code "27") (name "/GP15_EXT") (class "Default")
      (node (ref "J10") (pin "1") (pinfunction "1_1") (pintype "passive"))
      (node (ref "P3") (pin "2") (pinfunction "2_2") (pintype "passive"))
      (node (ref "R70") (pin "1") (pinfunction "1_1") (pintype "passive"))
    )
    (net (code "28") (name "/GP16") (class "Default")
      (node (ref "P5") (pin "3") (pinfunction "3_3") (pintype "passive"))
      (node (ref "U1") (pin "27") (pinfunction "GPIO16_27") (pintype "bidirectional"))
    )
    (net (code "29") (name "/GP17") (class "Default")
      (node (ref "P5") (pin "4") (pinfunction "4_4") (pintype "passive"))
      (node (ref "U1") (pin "28") (pinfunction "GPIO17_28") (pintype "bidirectional"))
    )
    (net (code "30") (name "/GP18") (class "Default")
      (node (ref "P5") (pin "5") (pinfunction "5_5") (pintype "passive"))
      (node (ref "U1") (pin "29") (pinfunction "GPIO18_29") (pintype "bidirectional"))
    )
    (net (code "31") (name "/GP19") (class "Default")
      (node (ref "P3") (pin "5") (pinfunction "5_5") (pintype "passive"))
      (node (ref "U1") (pin "30") (pinfunction "GPIO19_30") (pintype "bidirectional"))
    )
    (net (code "32") (name "/GP20") (class "Default")
      (node (ref "P5") (pin "6") (pinfunction "6_6") (pintype "passive"))
      (node (ref "U1") (pin "31") (pinfunction "GPIO20_31") (pintype "bidirectional"))
    )
    (net (code "33") (name "/GP21") (class "Default")
      (node (ref "P5") (pin "7") (pinfunction "7_7") (pintype "passive"))
      (node (ref "U1") (pin "32") (pinfunction "GPIO21_32") (pintype "bidirectional"))
    )
    (net (code "34") (name "/GP22") (class "Default")
      (node (ref "P5") (pin "8") (pinfunction "8_8") (pintype "passive"))
      (node (ref "U1") (pin "34") (pinfunction "GPIO22_34") (pintype "bidirectional"))
    )
    (net (code "35") (name "/GP23") (class "Default")
      (node (ref "P3") (pin "6") (pinfunction "6_6") (pintype "passive"))
      (node (ref "U1") (pin "35") (pinfunction "GPIO23_35") (pintype "bidirectional"))
    )
    (net (code "36") (name "/GP24") (class "Default")
      (node (ref "P3") (pin "1") (pinfunction "1_1") (pintype "passive"))
      (node (ref "U1") (pin "36") (pinfunction "GPIO24_36") (pintype "bidirectional"))
    )
    (net (code "40") (name "/MOD_DIR") (class "Default")
      (node (ref "U1") (pin "39") (pinfunction "G27/A1_39") (pintype "bidirectional"))
    )
    (net (code "41") (name "/NEOPIXEL0") (class "Default")
      (node (ref "U1") (pin "38") (pinfunction "G26/A0_38") (pintype "bidirectional"))
      (node (ref "U13") (pin "3") (pinfunction "2A_3") (pintype "input"))
    )
    (net (code "42") (name "/NEOPIXEL0_5V") (class "Default")
      (node (ref "P9") (pin "2") (pinfunction "2_2") (pintype "passive"))
      (node (ref "R11") (pin "1") (pinfunction "1_1") (pintype "passive"))
    )
    (net (code "43") (name "/NEOPIXEL1") (class "Default")
      (node (ref "U1") (pin "37") (pinfunction "GPIO25_37") (pintype "bidirectional"))
      (node (ref "U13") (pin "1") (pinfunction "1A_1") (pintype "input"))
    )
    (net (code "44") (name "/NEOPIXEL1_5V") (class "Default")
      (node (ref "J3") (pin "1") (pinfunction "1_1") (pintype "passive"))
      (node (ref "U13") (pin "6") (pinfunction "1Y_6") (pintype "output"))
    )
    (net (code "45") (name "/PICO_RUN") (class "Default")
      (node (ref "C23") (pin "2") (pinfunction "2_2") (pintype "passive"))
      (node (ref "P4") (pin "3") (pinfunction "3_3") (pintype "passive"))
      (node (ref "R19") (pin "1") (pinfunction "1_1") (pintype "passive"))
      (node (ref "SW1") (pin "2") (pinfunction "2_2") (pintype "passive"))
      (node (ref "U1") (pin "26") (pinfunction "RUN_26") (pintype "input"))
      (node (ref "U5") (pin "2") (pinfunction "~{RESET}_2") (pintype "input"))
    )
    (net (code "46") (name "/PICO_SWCLK") (class "Default")
      (node (ref "P7") (pin "4") (pinfunction "4_4") (pintype "passive"))
      (node (ref "U1") (pin "24") (pinfunction "SWCLK_24") (pintype "input"))
    )
    (net (code "47") (name "/PICO_SWDIO") (class "Default")
      (node (ref "P7") (pin "2") (pinfunction "2_2") (pintype "passive"))
      (node (ref "U1") (pin "25") (pinfunction "SWDIO_25") (pintype "input"))
    )
    (net (code "49") (name "/QSPI_SCLK") (class "Default")
      (node (ref "L1") (pin "6") (pinfunction "CLK_6") (pintype "passive"))
      (node (ref "U1") (pin "52") (pinfunction "QSPI_SCLK_52") (pintype "input"))
    )
    (net (code "50") (name "/QSPI_SD0") (class "Default")
      (node (ref "L1") (pin "5") (pinfunction "DI_(IO0)_5") (pintype "passive"))
      (node (ref "U1") (pin "53") (pinfunction "QSPI_SD0_53") (pintype "input"))
    )
    (net (code "51") (name "/QSPI_SD1") (class "Default")
      (node (ref "L1") (pin "2") (pinfunction "DO_(IO1)_2") (pintype "passive"))
      (node (ref "U1") (pin "55") (pinfunction "QSPI_SD1_55") (pintype "input"))
    )
    (net (code "52") (name "/QSPI_SD2") (class "Default")
      (node (ref "L1") (pin "3") (pinfunction "IO2_3") (pintype "passive"))
      (node (ref "U1") (pin "54") (pinfunction "QSPI_SD2_54") (pintype "input"))
    )
    (net (code "53") (name "/QSPI_SD3") (class "Default")
      (node (ref "L1") (pin "7") (pinfunction "IO_7") (pintype "passive"))
      (node (ref "U1") (pin "51") (pinfunction "QSPI_SD3_51") (pintype "input"))
    )
    (net (code "54") (name "/QSPI_SS") (class "Default")
      (node (ref "L1") (pin "1") (pinfunction "/CS_1") (pintype "passive"))
      (node (ref "R1") (pin "1") (pinfunction "1_1") (pintype "passive"))
      (node (ref "R2") (pin "2") (pinfunction "2_2") (pintype "passive"))
      (node (ref "U1") (pin "56") (pinfunction "QSPI_SS_N_56") (pintype "input"))
    )
    (net (code "55") (name "/RP_XIN") (class "Default")
      (node (ref "C5") (pin "1") (pinfunction "1_1") (pintype "passive"))
      (node (ref "U1") (pin "20") (pinfunction "XIN_20") (pintype "input"))
      (node (ref "Y1") (pin "1") (pinfunction "CRYSTAL_1_1") (pintype "passive"))
    )
    (net (code "56") (name "/RP_XOUT") (class "Default")
      (node (ref "R5") (pin "2") (pinfunction "2_2") (pintype "passive"))
      (node (ref "U1") (pin "21") (pinfunction "XOUT_21") (pintype "input"))
    )
    (net (code "57") (name "/SPI_CLK") (class "Default")
      (node (ref "U1") (pin "4") (pinfunction "GPIO2_4") (pintype "bidirectional"))
    )
    (net (code "58") (name "/SPI_CSn") (class "Default")
      (node (ref "U1") (pin "3") (pinfunction "GPIO1_3") (pintype "bidirectional"))
    )
    (net (code "59") (name "/SPI_PICO") (class "Default")
      (node (ref "U1") (pin "5") (pinfunction "GPIO3_5") (pintype "bidirectional"))
    )
    (net (code "60") (name "/SPI_POCI") (class "Default")
      (node (ref "U1") (pin "2") (pinfunction "GPIO0_2") (pintype "bidirectional"))
    )
    (net (code "67") (name "/UART1_RX") (class "Default")
      (node (ref "U1") (pin "12") (pinfunction "GPIO9_12") (pintype "input"))
    )
    (net (code "68") (name "/UART1_TX") (class "Default")
      (node (ref "U1") (pin "11") (pinfunction "GPIO8_11") (pintype "input"))
    )
    (net (code "69") (name "/USBC_CC1") (class "Default")
      (node (ref "J1") (pin "A5") (pinfunction "CC1_A5") (pintype "bidirectional"))
      (node (ref "R32") (pin "1") (pinfunction "1_1") (pintype "passive"))
    )
    (net (code "70") (name "/USBC_CC2") (class "Default")
      (node (ref "J1") (pin "B5") (pinfunction "CC2_B5") (pintype "bidirectional"))
      (node (ref "R31") (pin "1") (pinfunction "1_1") (pintype "passive"))
    )
    (net (code "71") (name "/USB_D_N") (class "Default")
      (node (ref "J1") (pin "A7") (pinfunction "DN1_A7") (pintype "bidirectional"))
      (node (ref "J1") (pin "B7") (pinfunction "DN2_B7") (pintype "bidirectional"))
      (node (ref "R4") (pin "1") (pinfunction "1_1") (pintype "passive"))
    )
    (net (code "72") (name "/USB_D_P") (class "Default")
      (node (ref "J1") (pin "A6") (pinfunction "DP1_A6") (pintype "bidirectional"))
      (node (ref "J1") (pin "B6") (pinfunction "DP2_B6") (pintype "bidirectional"))
      (node (ref "R3") (pin "1") (pinfunction "1_1") (pintype "passive"))
    )
    (net (code "73") (name "/USB_D_R_N") (class "Default")
      (node (ref "R4") (pin "2") (pinfunction "2_2") (pintype "passive"))
      (node (ref "U1") (pin "46") (pinfunction "USB_DM_46") (pintype "input"))
    )
    (net (code "74") (name "/USB_D_R_P") (class "Default")
      (node (ref "R3") (pin "2") (pinfunction "2_2") (pintype "passive"))
      (node (ref "U1") (pin "47") (pinfunction "USB_DP_47") (pintype "input"))
    )
    (net (code "75") (name "/W5500_INTn") (class "Default")
      (node (ref "U1") (pin "6") (pinfunction "GPIO4_6") (pintype "bidirectional"))
    )
    (net (code "79") (name "GND") (class "Default")
      (node (ref "C1") (pin "1") (pinfunction "1_1") (pintype "passive"))
      (node (ref "C10") (pin "1") (pinfunction "1_1") (pintype "passive"))
      (node (ref "C11") (pin "1") (pinfunction "1_1") (pintype "passive"))
      (node (ref "C12") (pin "1") (pinfunction "1_1") (pintype "passive"))
      (node (ref "C13") (pin "1") (pinfunction "1_1") (pintype "passive"))
      (node (ref "C14") (pin "1") (pinfunction "1_1") (pintype "passive"))
      (node (ref "C15") (pin "1") (pinfunction "1_1") (pintype "passive"))
      (node (ref "C17") (pin "1") (pinfunction "1_1") (pintype "passive"))
      (node (ref "C18") (pin "1") (pinfunction "1_1") (pintype "passive"))
      (node (ref "C19") (pin "1") (pinfunction "1_1") (pintype "passive"))
      (node (ref "C2") (pin "1") (pinfunction "1_1") (pintype "passive"))
      (node (ref "C20") (pin "1") (pinfunction "1_1") (pintype "passive"))
      (node (ref "C21") (pin "1") (pinfunction "1_1") (pintype "passive"))
      (node (ref "C23") (pin "1") (pinfunction "1_1") (pintype "passive"))
      (node (ref "C24") (pin "1") (pinfunction "1_1") (pintype "passive"))
      (node (ref "C25") (pin "1") (pinfunction "1_1") (pintype "passive"))
      (node (ref "C26") (pin "1") (pinfunction "1_1") (pintype "passive"))
      (node (ref "C29") (pin "1") (pinfunction "1_1") (pintype "passive"))
      (node (ref "C30") (pin "1") (pinfunction "1_1") (pintype "passive"))
      (node (ref "C5") (pin "2") (pinfunction "2_2") (pintype "passive"))
      (node (ref "C50") (pin "1") (pinfunction "1_1") (pintype "passive"))
      (node (ref "C51") (pin "1") (pinfunction "1_1") (pintype "passive"))
      (node (ref "C53") (pin "1") (pinfunction "1_1") (pintype "passive"))
      (node (ref "C54") (pin "2") (pinfunction "2_2") (pintype "passive"))
      (node (ref "C6") (pin "2") (pinfunction "2_2") (pintype "passive"))
      (node (ref "C7") (pin "1") (pinfunction "1_1") (pintype "passive"))
      (node (ref "C8") (pin "1") (pinfunction "1_1") (pintype "passive"))
      (node (ref "C9") (pin "1") (pinfunction "1_1") (pintype "passive"))
      (node (ref "D10") (pin "K") (pinfunction "K_K") (pintype "passive"))
      (node (ref "D13") (pin "1") (pinfunction "A_1") (pintype "passive"))
      (node (ref "D3") (pin "1") (pinfunction "A_1") (pintype "passive"))
      (node (ref "D4") (pin "1") (pinfunction "A_1") (pintype "passive"))
      (node (ref "D9") (pin "1") (pinfunction "A_1") (pintype "passive"))
      (node (ref "J1") (pin "A1B12") (pinfunction "GND_A1B12") (pintype "power_in"))
      (node (ref "J1") (pin "B1A12") (pinfunction "GND_B1A12") (pintype "power_in"))
      (node (ref "J1") (pin "S1") (pinfunction "SHIELD_S1") (pintype "passive"))
      (node (ref "J1") (pin "S2") (pinfunction "SHIELD_S2") (pintype "passive"))
      (node (ref "J1") (pin "S3") (pinfunction "SHIELD_S3") (pintype "passive"))
      (node (ref "J1") (pin "S4") (pinfunction "SHIELD_S4") (pintype "passive"))
      (node (ref "J2") (pin "2") (pinfunction "2_2") (pintype "passive"))
      (node (ref "J3") (pin "2") (pinfunction "2_2") (pintype "passive"))
      (node (ref "L1") (pin "4") (pinfunction "GND_4") (pintype "passive"))
      (node (ref "P3") (pin "7") (pinfunction "7_7") (pintype "passive"))
      (node (ref "P4") (pin "6") (pinfunction "6_6") (pintype "passive"))
      (node (ref "P4") (pin "7") (pinfunction "7_7") (pintype "passive"))
      (node (ref "P7") (pin "3") (pinfunction "3_3") (pintype "passive"))
      (node (ref "P7") (pin "5") (pinfunction "5_5") (pintype "passive"))
      (node (ref "P9") (pin "1") (pinfunction "1_1") (pintype "passive"))
      (node (ref "R31") (pin "2") (pinfunction "2_2") (pintype "passive"))
      (node (ref "R32") (pin "2") (pinfunction "2_2") (pintype "passive"))
      (node (ref "SW1") (pin "1") (pinfunction "1_1") (pintype "passive"))
      (node (ref "SW1") (pin "3") (pinfunction "3_3") (pintype "passive"))
      (node (ref "SW1") (pin "MP1") (pinfunction "MP1_MP1") (pintype "passive"))
      (node (ref "SW1") (pin "MP2") (pinfunction "MP2_MP2") (pintype "passive"))
      (node (ref "SW2") (pin "2") (pinfunction "2_2") (pintype "passive"))
      (node (ref "U1") (pin "19") (pinfunction "TESTEN_19") (pintype "input"))
      (node (ref "U1") (pin "57") (pinfunction "PAD_GND_57") (pintype "input"))
      (node (ref "U13") (pin "2") (pinfunction "GND_2") (pintype "power_in"))
      (node (ref "U5") (pin "1") (pinfunction "GND_1") (pintype "power_in"))
      (node (ref "VR2") (pin "1") (pinfunction "GND_1") (pintype "passive"))
      (node (ref "Y1") (pin "2") (pinfunction "GND_1_2") (pintype "passive"))
      (node (ref "Y1") (pin "4") (pinfunction "GND_2_4") (pintype "passive"))
    )
    (net (code "80") (name "INPUT_VCC") (class "Default")
      (node (ref "FUSE1") (pin "1") (pinfunction "1_1") (pintype "passive"))
      (node (ref "J2") (pin "1") (pinfunction "1_1") (pintype "passive"))
      (node (ref "P4") (pin "8") (pinfunction "8_8") (pintype "passive"))
      (node (ref "P9") (pin "3") (pinfunction "3_3") (pintype "passive"))
    )
    (net (code "81") (name "Net-(C29-Pad2)") (class "Default")
      (node (ref "C29") (pin "2") (pinfunction "2_2") (pintype "passive"))
      (node (ref "R17") (pin "1") (pinfunction "1_1") (pintype "passive"))
      (node (ref "R6") (pin "2") (pinfunction "2_2") (pintype "passive"))
    )
    (net (code "82") (name "Net-(C30-Pad2)") (class "Default")
      (node (ref "C30") (pin "2") (pinfunction "2_2") (pintype "passive"))
      (node (ref "R15") (pin "2") (pinfunction "2_2") (pintype "passive"))
      (node (ref "R29") (pin "1") (pinfunction "1_1") (pintype "passive"))
    )
    (net (code "83") (name "Net-(D10-PadA)") (class "Default")
      (node (ref "D10") (pin "A") (pinfunction "A_A") (pintype "passive"))
      (node (ref "R10") (pin "1") (pinfunction "1_1") (pintype "passive"))
    )
    (net (code "84") (name "Net-(R2-Pad1)") (class "Default")
      (node (ref "R2") (pin "1") (pinfunction "1_1") (pintype "passive"))
      (node (ref "SW2") (pin "1") (pinfunction "1_1") (pintype "passive"))
    )
    (net (code "85") (name "Net-(U13B-2Y)") (class "Default")
      (node (ref "R11") (pin "2") (pinfunction "2_2") (pintype "passive"))
      (node (ref "U13") (pin "4") (pinfunction "2Y_4") (pintype "output"))
    )
    (net (code "86") (name "Net-(Y1-CRYSTAL_2)") (class "Default")
      (node (ref "C6") (pin "1") (pinfunction "1_1") (pintype "passive"))
      (node (ref "R5") (pin "1") (pinfunction "1_1") (pintype "passive"))
      (node (ref "Y1") (pin "3") (pinfunction "CRYSTAL_2_3") (pintype "passive"))
    )
    (net (code "87") (name "Relay_VCC") (class "Default")
      (node (ref "D13") (pin "2") (pinfunction "K_2") (pintype "passive"))
      (node (ref "FUSE1") (pin "2") (pinfunction "2_2") (pintype "passive"))
    )
    (net (code "88") (name "VREG_1V1") (class "Default")
      (node (ref "C7") (pin "2") (pinfunction "2_2") (pintype "passive"))
      (node (ref "C8") (pin "2") (pinfunction "2_2") (pintype "passive"))
      (node (ref "C9") (pin "2") (pinfunction "2_2") (pintype "passive"))
      (node (ref "U1") (pin "23") (pinfunction "DVDD_23") (pintype "input"))
      (node (ref "U1") (pin "45") (pinfunction "VREG_VOUT_45") (pintype "input"))
      (node (ref "U1") (pin "50") (pinfunction "DVDD_50") (pintype "input"))
    )
    (net (code "89") (name "unconnected-(J1-SBU1-PadA8)") (class "Default")
      (node (ref "J1") (pin "A8") (pinfunction "SBU1_A8") (pintype "bidirectional"))
    )
    (net (code "90") (name "unconnected-(J1-SBU2-PadB8)") (class "Default")
      (node (ref "J1") (pin "B8") (pinfunction "SBU2_B8") (pintype "bidirectional"))
    )
    (net (code "91") (name "unconnected-(P4-Pad1)") (class "Default")
      (node (ref "P4") (pin "1") (pinfunction "1_1") (pintype "passive"))
    )
    (net (code "92") (name "unconnected-(P7-Pad6)") (class "Default")
      (node (ref "P7") (pin "6") (pinfunction "6_6") (pintype "passive"))
    )
    (net (code "93") (name "unconnected-(P7-Pad7)") (class "Default")
      (node (ref "P7") (pin "7") (pinfunction "7_7") (pintype "passive"))
    )
    (net (code "94") (name "unconnected-(P7-Pad8)") (class "Default")
      (node (ref "P7") (pin "8") (pinfunction "8_8") (pintype "passive"))
    )
    (net (code "95") (name "unconnected-(P7-Pad9)") (class "Default")
      (node (ref "P7") (pin "9") (pinfunction "9_9") (pintype "passive"))
    )
    (net (code "96") (name "unconnected-(P7-Pad10)") (class "Default")
      (node (ref "P7") (pin "10") (pinfunction "10_10") (pintype "passive"))
    )
  )
)
